# 06_NFC.net
KiCad netlist of a schematic drawn in Altium Designer
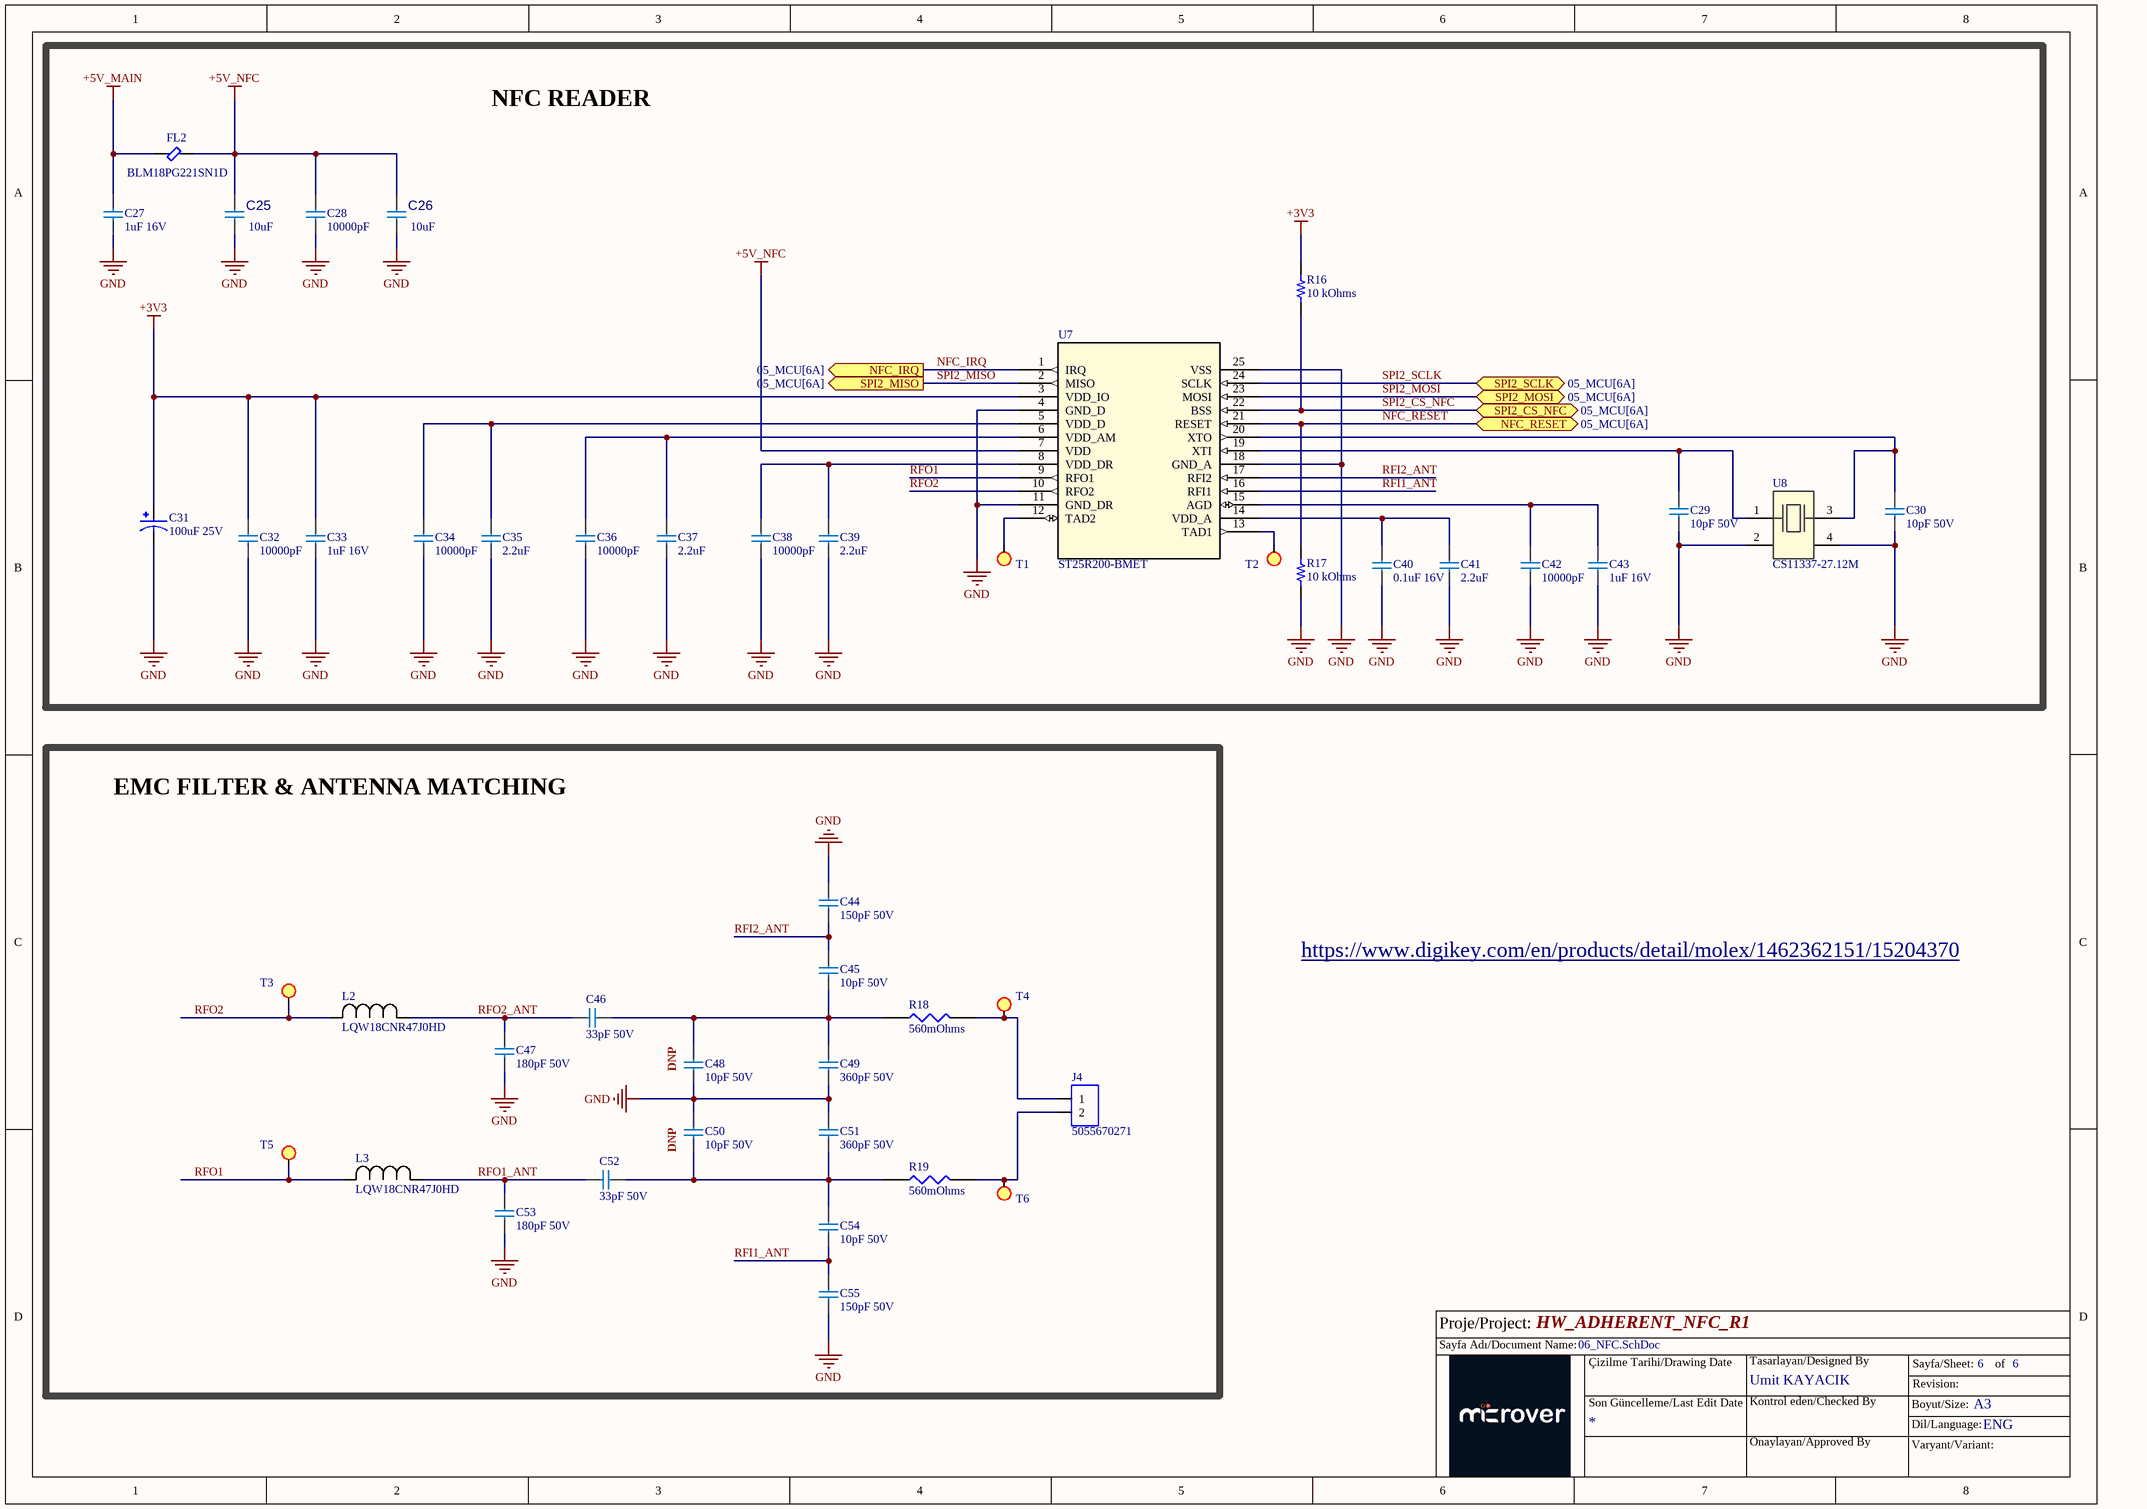
[diagram p0: 06_NFC.SchDoc]

(export (version "E")
  (design (tool "Eeschema 10.0.6"))
  (components
    (comp (ref "C25")
      (value "10uF")
      (footprint "CAPC1608X100N")
      (description "CAP CER 10UF 25V X5R 0603")
      (fields (field (name "VOLTAGE") "25V") (field (name "MANUFACTURER") "Murata Electronics North America"))
      (libsource (lib "HW_ADHERENT_NFC_R1_L2") (part "CAP1461"))
    )
    (comp (ref "C26")
      (value "10uF")
      (footprint "CAPC1608X100N")
      (description "CAP CER 10UF 25V X5R 0603")
      (fields (field (name "VOLTAGE") "25V") (field (name "MANUFACTURER") "Murata Electronics North America"))
      (libsource (lib "HW_ADHERENT_NFC_R1_L2") (part "CAP1461"))
    )
    (comp (ref "C27")
      (value "1uF 16V")
      (footprint "CAPC1608X100N")
      (description "Multilayer Ceramic Capacitors MLCC - SMD/SMT 0603 1.0uF 16volts X5R 10%")
      (libsource (lib "HW_ADHERENT_NFC_R1_L1") (part "VJ0603G105KXJCW1BC"))
    )
    (comp (ref "C28")
      (value "10000pF")
      (footprint "CAPC1608X100N")
      (description "10000 pF ±10% 16V Ceramic Capacitor X7R 0603 (1608 Metric)")
      (fields (field (name "MANUFACTURER") "KEMET") (field (name "JLCPCB PART#") "0603"))
      (libsource (lib "HW_ADHERENT_NFC_R1_L1") (part "C0603C103K4RECTU"))
    )
    (comp (ref "C29")
      (value "10pF 50V")
      (footprint "CAPC1608X100N")
      (description "10 pF ±1% 50V Ceramic Capacitor C0G, NP0 0603 (1608 Metric)")
      (fields (field (name "MANUFACTURER") "KEMET"))
      (libsource (lib "HW_ADHERENT_NFC_R1_L1") (part "C0603C100F5GACAUTO"))
    )
    (comp (ref "C30")
      (value "10pF 50V")
      (footprint "CAPC1608X100N")
      (description "10 pF ±1% 50V Ceramic Capacitor C0G, NP0 0603 (1608 Metric)")
      (fields (field (name "MANUFACTURER") "KEMET"))
      (libsource (lib "HW_ADHERENT_NFC_R1_L1") (part "C0603C100F5GACAUTO"))
    )
    (comp (ref "C31")
      (value "100uF 25V")
      (footprint "CAP_25SVPF100M")
      (description "100 µF 25 V Aluminum - Polymer Capacitors Radial, Can - SMD 24mOhm 5000 Hrs @ 105°C")
      (fields (field (name "MANUFACTURER") "Panasonic Industry") (field (name "JLCPCB PART#") "C136279"))
      (libsource (lib "HW_ADHERENT_NFC_R1_L1") (part "25SVPF100M"))
    )
    (comp (ref "C32")
      (value "10000pF")
      (footprint "CAPC1608X100N")
      (description "10000 pF ±10% 16V Ceramic Capacitor X7R 0603 (1608 Metric)")
      (fields (field (name "MANUFACTURER") "KEMET") (field (name "JLCPCB PART#") "0603"))
      (libsource (lib "HW_ADHERENT_NFC_R1_L1") (part "C0603C103K4RECTU"))
    )
    (comp (ref "C33")
      (value "1uF 16V")
      (footprint "CAPC1608X100N")
      (description "Multilayer Ceramic Capacitors MLCC - SMD/SMT 0603 1.0uF 16volts X5R 10%")
      (libsource (lib "HW_ADHERENT_NFC_R1_L1") (part "VJ0603G105KXJCW1BC"))
    )
    (comp (ref "C34")
      (value "10000pF")
      (footprint "CAPC1608X100N")
      (description "10000 pF ±10% 16V Ceramic Capacitor X7R 0603 (1608 Metric)")
      (fields (field (name "MANUFACTURER") "KEMET") (field (name "JLCPCB PART#") "0603"))
      (libsource (lib "HW_ADHERENT_NFC_R1_L1") (part "C0603C103K4RECTU"))
    )
    (comp (ref "C35")
      (value "2.2uF")
      (footprint "CAPC1608X100N")
      (description "2.2 µF ±10% 25V Ceramic Capacitor X5R 0603 (1608 Metric)")
      (fields
        (field (name "MANUFACTURER") "Walsin Technology Corporation")
        (field (name "JLCPCB PART#") "C237194")
      )
      (libsource (lib "HW_ADHERENT_NFC_R1_L1") (part "0603X225K250CT"))
    )
    (comp (ref "C36")
      (value "10000pF")
      (footprint "CAPC1608X100N")
      (description "10000 pF ±10% 16V Ceramic Capacitor X7R 0603 (1608 Metric)")
      (fields (field (name "MANUFACTURER") "KEMET") (field (name "JLCPCB PART#") "0603"))
      (libsource (lib "HW_ADHERENT_NFC_R1_L1") (part "C0603C103K4RECTU"))
    )
    (comp (ref "C37")
      (value "2.2uF")
      (footprint "CAPC1608X100N")
      (description "2.2 µF ±10% 25V Ceramic Capacitor X5R 0603 (1608 Metric)")
      (fields
        (field (name "MANUFACTURER") "Walsin Technology Corporation")
        (field (name "JLCPCB PART#") "C237194")
      )
      (libsource (lib "HW_ADHERENT_NFC_R1_L1") (part "0603X225K250CT"))
    )
    (comp (ref "C38")
      (value "10000pF")
      (footprint "CAPC1608X100N")
      (description "10000 pF ±10% 16V Ceramic Capacitor X7R 0603 (1608 Metric)")
      (fields (field (name "MANUFACTURER") "KEMET") (field (name "JLCPCB PART#") "0603"))
      (libsource (lib "HW_ADHERENT_NFC_R1_L1") (part "C0603C103K4RECTU"))
    )
    (comp (ref "C39")
      (value "2.2uF")
      (footprint "CAPC1608X100N")
      (description "2.2 µF ±10% 25V Ceramic Capacitor X5R 0603 (1608 Metric)")
      (fields
        (field (name "MANUFACTURER") "Walsin Technology Corporation")
        (field (name "JLCPCB PART#") "C237194")
      )
      (libsource (lib "HW_ADHERENT_NFC_R1_L1") (part "0603X225K250CT"))
    )
    (comp (ref "C40")
      (value "0.1uF 16V")
      (footprint "CAPC1608X100N")
      (description "0.1 µF ±10% 16V Ceramic Capacitor X7R 0603 (1608 Metric)")
      (fields (field (name "MANUFACTURER") "Vishay Vitramon"))
      (libsource (lib "HW_ADHERENT_NFC_R1_L1") (part "VJ0603Y104KXJAC"))
    )
    (comp (ref "C41")
      (value "2.2uF")
      (footprint "CAPC1608X100N")
      (description "2.2 µF ±10% 25V Ceramic Capacitor X5R 0603 (1608 Metric)")
      (fields
        (field (name "MANUFACTURER") "Walsin Technology Corporation")
        (field (name "JLCPCB PART#") "C237194")
      )
      (libsource (lib "HW_ADHERENT_NFC_R1_L1") (part "0603X225K250CT"))
    )
    (comp (ref "C42")
      (value "10000pF")
      (footprint "CAPC1608X100N")
      (description "10000 pF ±10% 16V Ceramic Capacitor X7R 0603 (1608 Metric)")
      (fields (field (name "MANUFACTURER") "KEMET") (field (name "JLCPCB PART#") "0603"))
      (libsource (lib "HW_ADHERENT_NFC_R1_L1") (part "C0603C103K4RECTU"))
    )
    (comp (ref "C43")
      (value "1uF 16V")
      (footprint "CAPC1608X100N")
      (description "Multilayer Ceramic Capacitors MLCC - SMD/SMT 0603 1.0uF 16volts X5R 10%")
      (libsource (lib "HW_ADHERENT_NFC_R1_L1") (part "VJ0603G105KXJCW1BC"))
    )
    (comp (ref "C44")
      (value "150pF 50V")
      (footprint "CAPC1005X04L")
      (description "150 pF ±2% 50V Ceramic Capacitor C0G, NP0 0402 (1005 Metric)")
      (fields (field (name "MANUFACTURER") "Cal-Chip Electronics, Inc."))
      (libsource (lib "HW_ADHERENT_NFC_R1_L1") (part "GMC04CG151G50NT"))
    )
    (comp (ref "C45")
      (value "10pF 50V")
      (footprint "CAPC1005X04L")
      (description "CAP0402 COG 10PF 2% 50V")
      (fields (field (name "MANUFACTURER") "Cal-Chip Electronics, Inc."))
      (libsource (lib "HW_ADHERENT_NFC_R1_L1") (part "GMC04CG100G50NT"))
    )
    (comp (ref "C46")
      (value "33pF 50V")
      (footprint "CAPC1005X04L")
      (description "33 pF ±1% 50V Ceramic Capacitor C0G, NP0 0402 (1005 Metric)")
      (fields (field (name "MANUFACTURER") "Cal-Chip Electronics, Inc."))
      (libsource (lib "HW_ADHERENT_NFC_R1_L1") (part "GMC04CG330F50NT"))
    )
    (comp (ref "C47")
      (value "180pF 50V")
      (footprint "CAPC1005X04L")
      (description "180 pF ±1% 50V Ceramic Capacitor C0G, NP0 0402 (1005 Metric)")
      (libsource (lib "HW_ADHERENT_NFC_R1_L1") (part "GMC04CG181F50NT"))
    )
    (comp (ref "C48")
      (value "10pF 50V")
      (footprint "CAPC1005X04L")
      (description "CAP0402 COG 10PF 2% 50V")
      (fields (field (name "MANUFACTURER") "Cal-Chip Electronics, Inc."))
      (libsource (lib "HW_ADHERENT_NFC_R1_L1") (part "GMC04CG100G50NT"))
    )
    (comp (ref "C49")
      (value "360pF 50V")
      (footprint "CAPC1005X04L")
      (description "360 pF ±5% 50V Ceramic Capacitor C0G, NP0 0402 (1005 Metric)")
      (fields (field (name "MANUFACTURER") "Cal-Chip Electronics, Inc."))
      (libsource (lib "HW_ADHERENT_NFC_R1_L1") (part "GMC04CG361J50NT"))
    )
    (comp (ref "C50")
      (value "10pF 50V")
      (footprint "CAPC1005X04L")
      (description "CAP0402 COG 10PF 2% 50V")
      (fields (field (name "MANUFACTURER") "Cal-Chip Electronics, Inc."))
      (libsource (lib "HW_ADHERENT_NFC_R1_L1") (part "GMC04CG100G50NT"))
    )
    (comp (ref "C51")
      (value "360pF 50V")
      (footprint "CAPC1005X04L")
      (description "360 pF ±5% 50V Ceramic Capacitor C0G, NP0 0402 (1005 Metric)")
      (fields (field (name "MANUFACTURER") "Cal-Chip Electronics, Inc."))
      (libsource (lib "HW_ADHERENT_NFC_R1_L1") (part "GMC04CG361J50NT"))
    )
    (comp (ref "C52")
      (value "33pF 50V")
      (footprint "CAPC1005X04L")
      (description "33 pF ±1% 50V Ceramic Capacitor C0G, NP0 0402 (1005 Metric)")
      (fields (field (name "MANUFACTURER") "Cal-Chip Electronics, Inc."))
      (libsource (lib "HW_ADHERENT_NFC_R1_L1") (part "GMC04CG330F50NT"))
    )
    (comp (ref "C53")
      (value "180pF 50V")
      (footprint "CAPC1005X04L")
      (description "180 pF ±1% 50V Ceramic Capacitor C0G, NP0 0402 (1005 Metric)")
      (libsource (lib "HW_ADHERENT_NFC_R1_L1") (part "GMC04CG181F50NT"))
    )
    (comp (ref "C54")
      (value "10pF 50V")
      (footprint "CAPC1005X04L")
      (description "CAP0402 COG 10PF 2% 50V")
      (fields (field (name "MANUFACTURER") "Cal-Chip Electronics, Inc."))
      (libsource (lib "HW_ADHERENT_NFC_R1_L1") (part "GMC04CG100G50NT"))
    )
    (comp (ref "C55")
      (value "150pF 50V")
      (footprint "CAPC1005X04L")
      (description "150 pF ±2% 50V Ceramic Capacitor C0G, NP0 0402 (1005 Metric)")
      (fields (field (name "MANUFACTURER") "Cal-Chip Electronics, Inc."))
      (libsource (lib "HW_ADHERENT_NFC_R1_L1") (part "GMC04CG151G50NT"))
    )
    (comp (ref "FL2")
      (value "BLM18PG221SN1D")
      (footprint "BEADC1608X95N")
      (description "220 Ohms @ 100 MHz 1 Power Line Ferrite Bead 0603 (1608 Metric) 1.4A 100mOhm")
      (fields (field (name "MF") "Murata"))
      (libsource (lib "HW_ADHERENT_NFC_R1_L1") (part "BLM18PG221SN1D"))
    )
    (comp (ref "J4")
      (value "5055670271")
      (footprint "CONN_505567_02_MOL")
      (description "Connector Header Surface Mount, Right Angle 2 position 0.049\" (1.25mm)")
      (fields (field (name "MANUFACTURER") "Molex"))
      (libsource (lib "HW_ADHERENT_NFC_R1_L1") (part "5055670271"))
    )
    (comp (ref "L2")
      (value "LQW18CNR47J0HD")
      (footprint "IND_LQW18CN_0H_MUR")
      (description "Description")
      (fields (field (name "COPYRIGHT") "Copyright (C) 2025 Ultra Librarian. All rights reserved."))
      (libsource (lib "HW_ADHERENT_NFC_R1_L1") (part "LQW18CNR47J0HD"))
    )
    (comp (ref "L3")
      (value "LQW18CNR47J0HD")
      (footprint "IND_LQW18CN_0H_MUR")
      (description "Description")
      (fields (field (name "COPYRIGHT") "Copyright (C) 2025 Ultra Librarian. All rights reserved."))
      (libsource (lib "HW_ADHERENT_NFC_R1_L1") (part "LQW18CNR47J0HD"))
    )
    (comp (ref "R16")
      (value "10 kOhms")
      (footprint "RES 0603_1608")
      (description "RES 10K OHM 0.1% 1/16W 0603")
      (fields
        (field (name "PART NUMBER") "RNCS0603BKE10K0")
        (field (name "MANUFACTURER") "Stackpole Electronics Inc")
      )
      (libsource (lib "HW_ADHERENT_NFC_R1_L2") (part "RNCS0603BKE10K0_1"))
    )
    (comp (ref "R17")
      (value "10 kOhms")
      (footprint "RES 0603_1608")
      (description "RES 10K OHM 0.1% 1/16W 0603")
      (fields
        (field (name "PART NUMBER") "RNCS0603BKE10K0")
        (field (name "MANUFACTURER") "Stackpole Electronics Inc")
      )
      (libsource (lib "HW_ADHERENT_NFC_R1_L2") (part "RNCS0603BKE10K0_1"))
    )
    (comp (ref "R18")
      (value "560mOhms")
      (footprint "RES_0402")
      (description "560 mOhms ±1% 0.125W, 1/8W Chip Resistor 0402 (1005 Metric) Current Sense Thick Film")
      (fields (field (name "MANUFACTURER") "TE Connectivity Passive Product"))
      (libsource (lib "HW_ADHERENT_NFC_R1_L1") (part "RLP73K1ER56FTDF"))
    )
    (comp (ref "R19")
      (value "560mOhms")
      (footprint "RES_0402")
      (description "560 mOhms ±1% 0.125W, 1/8W Chip Resistor 0402 (1005 Metric) Current Sense Thick Film")
      (fields (field (name "MANUFACTURER") "TE Connectivity Passive Product"))
      (libsource (lib "HW_ADHERENT_NFC_R1_L1") (part "RLP73K1ER56FTDF"))
    )
    (comp (ref "T1")
      (value "SMD")
      (footprint "TEST_POINT")
      (libsource (lib "HW_ADHERENT_NFC_R1_L1") (part "TP"))
    )
    (comp (ref "T2")
      (value "SMD")
      (footprint "TEST_POINT")
      (libsource (lib "HW_ADHERENT_NFC_R1_L1") (part "TP"))
    )
    (comp (ref "T3")
      (value "SMD")
      (footprint "TEST_POINT")
      (libsource (lib "HW_ADHERENT_NFC_R1_L1") (part "TP"))
    )
    (comp (ref "T4")
      (value "SMD")
      (footprint "TEST_POINT")
      (libsource (lib "HW_ADHERENT_NFC_R1_L1") (part "TP"))
    )
    (comp (ref "T5")
      (value "SMD")
      (footprint "TEST_POINT")
      (libsource (lib "HW_ADHERENT_NFC_R1_L1") (part "TP"))
    )
    (comp (ref "T6")
      (value "SMD")
      (footprint "TEST_POINT")
      (libsource (lib "HW_ADHERENT_NFC_R1_L1") (part "TP"))
    )
    (comp (ref "U7")
      (value "ST25R200-BMET")
      (footprint "UFQFPN24_STM")
      (description "Powerful general-purpose NFC reader for consumer and industrial applications")
      (fields (field (name "COPYRIGHT") "Copyright (C) 2025 Ultra Librarian. All rights reserved."))
      (libsource (lib "HW_ADHERENT_NFC_R1_L1") (part "ST25R200-BMET"))
    )
    (comp (ref "U8")
      (value "CS11337-27.12M")
      (footprint "NX2016SA2712MHZEXS00ACS11337")
      (description "27.12 MHz ±30ppm Crystal 6pF 60 Ohms 4-SMD, No Lead")
      (libsource (lib "HW_ADHERENT_NFC_R1_L1") (part "CS11337-27.12M"))
    )
  )
  (nets
    (net (code "1") (name "+3V3") (class "Default")
      (node (ref "C31") (pin "1") (pinfunction "1_1") (pintype "passive"))
      (node (ref "C32") (pin "2") (pinfunction "2_2") (pintype "passive"))
      (node (ref "C33") (pin "2") (pinfunction "2_2") (pintype "passive"))
      (node (ref "R16") (pin "2") (pinfunction "2_2") (pintype "passive"))
      (node (ref "U7") (pin "3") (pinfunction "VDD_IO_3") (pintype "power_in"))
    )
    (net (code "2") (name "+5V_MAIN") (class "Default")
      (node (ref "C27") (pin "2") (pinfunction "2_2") (pintype "passive"))
      (node (ref "FL2") (pin "1") (pinfunction "1_1") (pintype "passive"))
    )
    (net (code "3") (name "+5V_NFC") (class "Default")
      (node (ref "C25") (pin "2") (pinfunction "2_2") (pintype "passive"))
      (node (ref "C26") (pin "2") (pinfunction "2_2") (pintype "passive"))
      (node (ref "C28") (pin "2") (pinfunction "2_2") (pintype "passive"))
      (node (ref "FL2") (pin "2") (pinfunction "2_2") (pintype "passive"))
      (node (ref "U7") (pin "7") (pinfunction "VDD_7") (pintype "power_in"))
    )
    (net (code "4") (name "/NFC_IRQ") (class "Default")
      (node (ref "U7") (pin "1") (pinfunction "IRQ_1") (pintype "output"))
    )
    (net (code "5") (name "/NFC_RESET") (class "Default")
      (node (ref "R17") (pin "2") (pinfunction "2_2") (pintype "passive"))
      (node (ref "U7") (pin "21") (pinfunction "RESET_21") (pintype "input"))
    )
    (net (code "6") (name "/RFI1_ANT") (class "Default")
      (node (ref "C54") (pin "1") (pinfunction "1_1") (pintype "passive"))
      (node (ref "C55") (pin "2") (pinfunction "2_2") (pintype "passive"))
      (node (ref "U7") (pin "16") (pinfunction "RFI1_16") (pintype "input"))
    )
    (net (code "7") (name "/RFI2_ANT") (class "Default")
      (node (ref "C44") (pin "1") (pinfunction "1_1") (pintype "passive"))
      (node (ref "C45") (pin "2") (pinfunction "2_2") (pintype "passive"))
      (node (ref "U7") (pin "17") (pinfunction "RFI2_17") (pintype "input"))
    )
    (net (code "8") (name "/RFO1") (class "Default")
      (node (ref "L3") (pin "1") (pinfunction "1_1") (pintype "passive"))
      (node (ref "T5") (pin "1") (pinfunction "TP_1") (pintype "passive"))
      (node (ref "U7") (pin "9") (pinfunction "RFO1_9") (pintype "output"))
    )
    (net (code "9") (name "/RFO1_ANT") (class "Default")
      (node (ref "C52") (pin "2") (pinfunction "2_2") (pintype "passive"))
      (node (ref "C53") (pin "2") (pinfunction "2_2") (pintype "passive"))
      (node (ref "L3") (pin "2") (pinfunction "2_2") (pintype "passive"))
    )
    (net (code "10") (name "/RFO2") (class "Default")
      (node (ref "L2") (pin "1") (pinfunction "1_1") (pintype "passive"))
      (node (ref "T3") (pin "1") (pinfunction "TP_1") (pintype "passive"))
      (node (ref "U7") (pin "10") (pinfunction "RFO2_10") (pintype "output"))
    )
    (net (code "11") (name "/RFO2_ANT") (class "Default")
      (node (ref "C46") (pin "2") (pinfunction "2_2") (pintype "passive"))
      (node (ref "C47") (pin "2") (pinfunction "2_2") (pintype "passive"))
      (node (ref "L2") (pin "2") (pinfunction "2_2") (pintype "passive"))
    )
    (net (code "12") (name "/SPI2_CS_NFC") (class "Default")
      (node (ref "R16") (pin "1") (pinfunction "1_1") (pintype "passive"))
      (node (ref "U7") (pin "22") (pinfunction "BSS_22") (pintype "input"))
    )
    (net (code "13") (name "/SPI2_MISO") (class "Default")
      (node (ref "U7") (pin "2") (pinfunction "MISO_2") (pintype "output"))
    )
    (net (code "14") (name "/SPI2_MOSI") (class "Default")
      (node (ref "U7") (pin "23") (pinfunction "MOSI_23") (pintype "input"))
    )
    (net (code "15") (name "/SPI2_SCLK") (class "Default")
      (node (ref "U7") (pin "24") (pinfunction "SCLK_24") (pintype "input"))
    )
    (net (code "16") (name "GND") (class "Default")
      (node (ref "C25") (pin "1") (pinfunction "_1") (pintype "passive"))
      (node (ref "C26") (pin "1") (pinfunction "_1") (pintype "passive"))
      (node (ref "C27") (pin "1") (pinfunction "1_1") (pintype "passive"))
      (node (ref "C28") (pin "1") (pinfunction "1_1") (pintype "passive"))
      (node (ref "C29") (pin "1") (pinfunction "1_1") (pintype "passive"))
      (node (ref "C30") (pin "1") (pinfunction "1_1") (pintype "passive"))
      (node (ref "C31") (pin "2") (pinfunction "2_2") (pintype "passive"))
      (node (ref "C32") (pin "1") (pinfunction "1_1") (pintype "passive"))
      (node (ref "C33") (pin "1") (pinfunction "1_1") (pintype "passive"))
      (node (ref "C34") (pin "1") (pinfunction "1_1") (pintype "passive"))
      (node (ref "C35") (pin "1") (pinfunction "1_1") (pintype "passive"))
      (node (ref "C36") (pin "1") (pinfunction "1_1") (pintype "passive"))
      (node (ref "C37") (pin "1") (pinfunction "1_1") (pintype "passive"))
      (node (ref "C38") (pin "1") (pinfunction "1_1") (pintype "passive"))
      (node (ref "C39") (pin "1") (pinfunction "1_1") (pintype "passive"))
      (node (ref "C40") (pin "1") (pinfunction "1_1") (pintype "passive"))
      (node (ref "C41") (pin "1") (pinfunction "1_1") (pintype "passive"))
      (node (ref "C42") (pin "1") (pinfunction "1_1") (pintype "passive"))
      (node (ref "C43") (pin "1") (pinfunction "1_1") (pintype "passive"))
      (node (ref "C44") (pin "2") (pinfunction "2_2") (pintype "passive"))
      (node (ref "C47") (pin "1") (pinfunction "1_1") (pintype "passive"))
      (node (ref "C48") (pin "1") (pinfunction "1_1") (pintype "passive"))
      (node (ref "C49") (pin "1") (pinfunction "1_1") (pintype "passive"))
      (node (ref "C50") (pin "2") (pinfunction "2_2") (pintype "passive"))
      (node (ref "C51") (pin "2") (pinfunction "2_2") (pintype "passive"))
      (node (ref "C53") (pin "1") (pinfunction "1_1") (pintype "passive"))
      (node (ref "C55") (pin "1") (pinfunction "1_1") (pintype "passive"))
      (node (ref "R17") (pin "1") (pinfunction "1_1") (pintype "passive"))
      (node (ref "U7") (pin "11") (pinfunction "GND_DR_11") (pintype "power_in"))
      (node (ref "U7") (pin "18") (pinfunction "GND_A_18") (pintype "power_in"))
      (node (ref "U7") (pin "25") (pinfunction "VSS_25") (pintype "power_in"))
      (node (ref "U7") (pin "4") (pinfunction "GND_D_4") (pintype "power_in"))
      (node (ref "U8") (pin "2") (pinfunction "GND_1_2") (pintype "passive"))
      (node (ref "U8") (pin "4") (pinfunction "GND_2_4") (pintype "passive"))
    )
    (net (code "17") (name "Net-(C45-Pad1)") (class "Default")
      (node (ref "C45") (pin "1") (pinfunction "1_1") (pintype "passive"))
      (node (ref "C46") (pin "1") (pinfunction "1_1") (pintype "passive"))
      (node (ref "C48") (pin "2") (pinfunction "2_2") (pintype "passive"))
      (node (ref "C49") (pin "2") (pinfunction "2_2") (pintype "passive"))
      (node (ref "R18") (pin "1") (pinfunction "1_1") (pintype "passive"))
    )
    (net (code "18") (name "Net-(C50-Pad1)") (class "Default")
      (node (ref "C50") (pin "1") (pinfunction "1_1") (pintype "passive"))
      (node (ref "C51") (pin "1") (pinfunction "1_1") (pintype "passive"))
      (node (ref "C52") (pin "1") (pinfunction "1_1") (pintype "passive"))
      (node (ref "C54") (pin "2") (pinfunction "2_2") (pintype "passive"))
      (node (ref "R19") (pin "1") (pinfunction "1_1") (pintype "passive"))
    )
    (net (code "19") (name "Net-(T1-TP)") (class "Default")
      (node (ref "T1") (pin "1") (pinfunction "TP_1") (pintype "passive"))
      (node (ref "U7") (pin "12") (pinfunction "TAD2_12") (pintype "bidirectional"))
    )
    (net (code "20") (name "Net-(T2-TP)") (class "Default")
      (node (ref "T2") (pin "1") (pinfunction "TP_1") (pintype "passive"))
      (node (ref "U7") (pin "13") (pinfunction "TAD1_13") (pintype "output"))
    )
    (net (code "21") (name "Net-(T4-TP)") (class "Default")
      (node (ref "J4") (pin "1") (pinfunction "1_1") (pintype "passive"))
      (node (ref "R18") (pin "2") (pinfunction "2_2") (pintype "passive"))
      (node (ref "T4") (pin "1") (pinfunction "TP_1") (pintype "passive"))
    )
    (net (code "22") (name "Net-(T6-TP)") (class "Default")
      (node (ref "J4") (pin "2") (pinfunction "2_2") (pintype "passive"))
      (node (ref "R19") (pin "2") (pinfunction "2_2") (pintype "passive"))
      (node (ref "T6") (pin "1") (pinfunction "TP_1") (pintype "passive"))
    )
    (net (code "23") (name "Net-(U7-AGD)") (class "Default")
      (node (ref "C42") (pin "2") (pinfunction "2_2") (pintype "passive"))
      (node (ref "C43") (pin "2") (pinfunction "2_2") (pintype "passive"))
      (node (ref "U7") (pin "15") (pinfunction "AGD_15") (pintype "bidirectional"))
    )
    (net (code "24") (name "Net-(U7-VDD_A)") (class "Default")
      (node (ref "C40") (pin "2") (pinfunction "2_2") (pintype "passive"))
      (node (ref "C41") (pin "2") (pinfunction "2_2") (pintype "passive"))
      (node (ref "U7") (pin "14") (pinfunction "VDD_A_14") (pintype "power_in"))
    )
    (net (code "25") (name "Net-(U7-VDD_AM)") (class "Default")
      (node (ref "C36") (pin "2") (pinfunction "2_2") (pintype "passive"))
      (node (ref "C37") (pin "2") (pinfunction "2_2") (pintype "passive"))
      (node (ref "U7") (pin "6") (pinfunction "VDD_AM_6") (pintype "power_in"))
    )
    (net (code "26") (name "Net-(U7-VDD_D)") (class "Default")
      (node (ref "C34") (pin "2") (pinfunction "2_2") (pintype "passive"))
      (node (ref "C35") (pin "2") (pinfunction "2_2") (pintype "passive"))
      (node (ref "U7") (pin "5") (pinfunction "VDD_D_5") (pintype "power_in"))
    )
    (net (code "27") (name "Net-(U7-VDD_DR)") (class "Default")
      (node (ref "C38") (pin "2") (pinfunction "2_2") (pintype "passive"))
      (node (ref "C39") (pin "2") (pinfunction "2_2") (pintype "passive"))
      (node (ref "U7") (pin "8") (pinfunction "VDD_DR_8") (pintype "power_in"))
    )
    (net (code "28") (name "Net-(U7-XTI)") (class "Default")
      (node (ref "C29") (pin "2") (pinfunction "2_2") (pintype "passive"))
      (node (ref "U7") (pin "19") (pinfunction "XTI_19") (pintype "input"))
      (node (ref "U8") (pin "1") (pinfunction "CRYSTAL_1_1") (pintype "passive"))
    )
    (net (code "29") (name "Net-(U7-XTO)") (class "Default")
      (node (ref "C30") (pin "2") (pinfunction "2_2") (pintype "passive"))
      (node (ref "U7") (pin "20") (pinfunction "XTO_20") (pintype "output"))
      (node (ref "U8") (pin "3") (pinfunction "CRYSTAL_2_3") (pintype "passive"))
    )
  )
)
